# Conn_pcb6.net
KiCad netlist of a schematic drawn in EAGLE
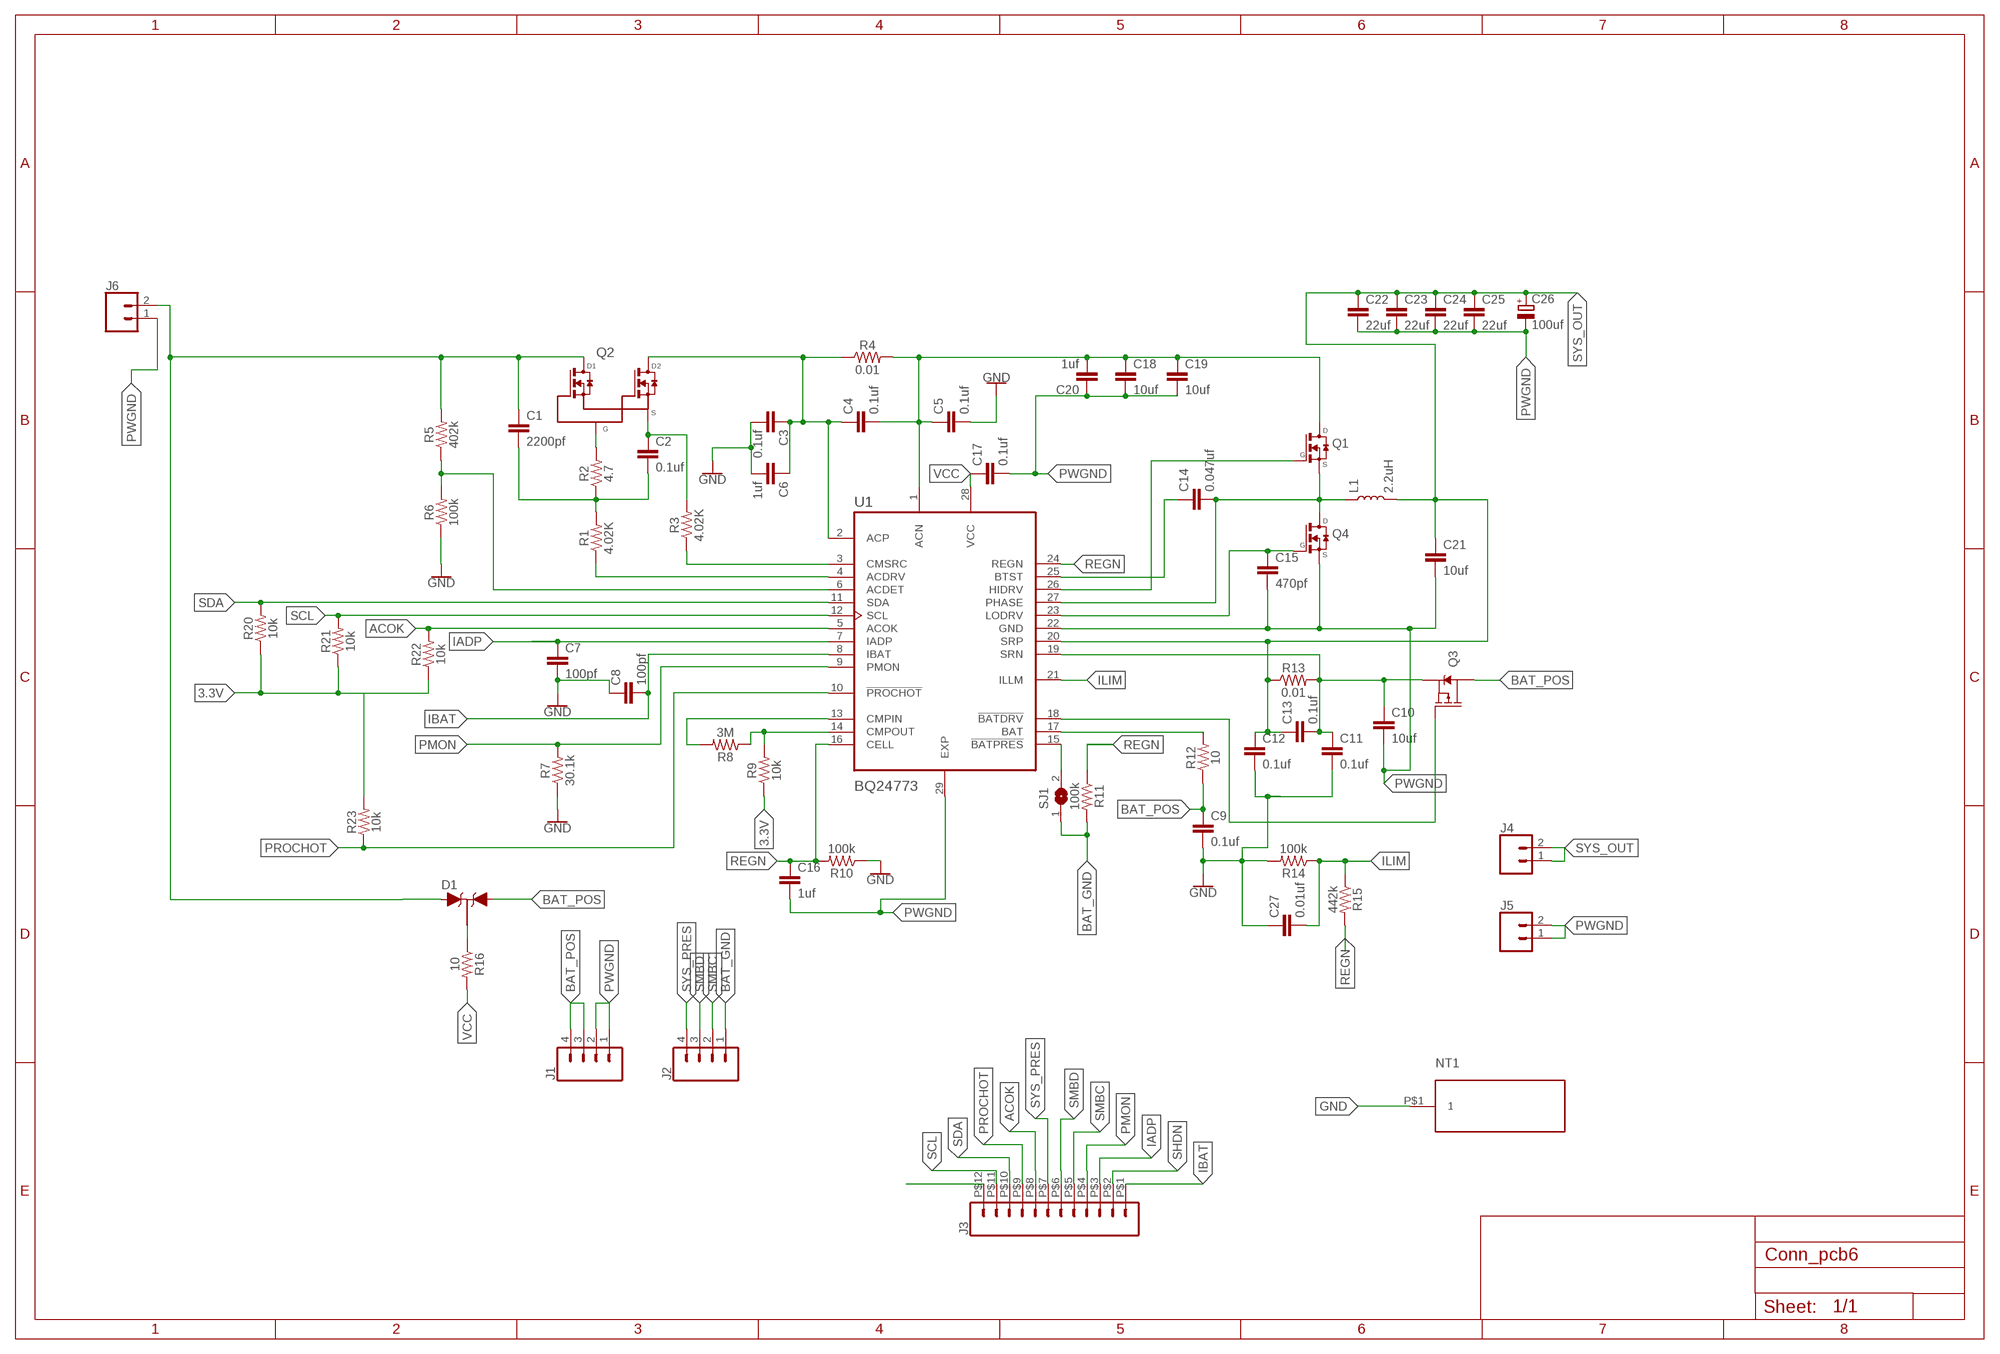
[diagram p0: schematic, sheet 1]

(export (version "E")
  (design (tool "Eeschema 10.0.6"))
  (components
    (comp (ref "C1")
      (value "2200pf")
      (footprint "eagle-import:CAPC1005X50")
      (libsource (lib "eagle-import") (part "CAP0402"))
    )
    (comp (ref "C2")
      (value "0.1uf")
      (footprint "eagle-import:CAPC1005X50")
      (libsource (lib "eagle-import") (part "CAP0402"))
    )
    (comp (ref "C3")
      (value "0.1uf")
      (footprint "eagle-import:CAPC1005X50")
      (libsource (lib "eagle-import") (part "CAP0402"))
    )
    (comp (ref "C4")
      (value "0.1uf")
      (footprint "eagle-import:CAPC1005X50")
      (libsource (lib "eagle-import") (part "CAP0402"))
    )
    (comp (ref "C5")
      (value "0.1uf")
      (footprint "eagle-import:CAPC1005X50")
      (libsource (lib "eagle-import") (part "CAP0402"))
    )
    (comp (ref "C6")
      (value "1uf")
      (footprint "eagle-import:CAPC1005X50")
      (libsource (lib "eagle-import") (part "CAP0402"))
    )
    (comp (ref "C7")
      (value "100pf")
      (footprint "eagle-import:CAPC1005X50")
      (libsource (lib "eagle-import") (part "CAP0402"))
    )
    (comp (ref "C8")
      (value "100pf")
      (footprint "eagle-import:CAPC1005X50")
      (libsource (lib "eagle-import") (part "CAP0402"))
    )
    (comp (ref "C9")
      (value "0.1uf")
      (footprint "eagle-import:CAPC1005X50")
      (libsource (lib "eagle-import") (part "CAP0402"))
    )
    (comp (ref "C10")
      (value "10uf")
      (footprint "eagle-import:C0805K")
      (libsource (lib "eagle-import") (part "C-EUC0805K"))
    )
    (comp (ref "C11")
      (value "0.1uf")
      (footprint "eagle-import:CAPC1005X50")
      (libsource (lib "eagle-import") (part "CAP0402"))
    )
    (comp (ref "C12")
      (value "0.1uf")
      (footprint "eagle-import:CAPC1005X50")
      (libsource (lib "eagle-import") (part "CAP0402"))
    )
    (comp (ref "C13")
      (value "0.1uf")
      (footprint "eagle-import:CAPC1005X50")
      (libsource (lib "eagle-import") (part "CAP0402"))
    )
    (comp (ref "C14")
      (value "0.047uf")
      (footprint "eagle-import:CAPC1005X50")
      (libsource (lib "eagle-import") (part "CAP0402"))
    )
    (comp (ref "C15")
      (value "470pf")
      (footprint "eagle-import:CAPC1005X50")
      (libsource (lib "eagle-import") (part "CAP0402"))
    )
    (comp (ref "C16")
      (value "1uf")
      (footprint "eagle-import:CAPC1005X50")
      (libsource (lib "eagle-import") (part "CAP0402"))
    )
    (comp (ref "C17")
      (value "0.1uf")
      (footprint "eagle-import:CAPC1005X50")
      (libsource (lib "eagle-import") (part "CAP0402"))
    )
    (comp (ref "C18")
      (value "10uf")
      (footprint "eagle-import:C0805K")
      (libsource (lib "eagle-import") (part "C-EUC0805K"))
    )
    (comp (ref "C19")
      (value "10uf")
      (footprint "eagle-import:C0805K")
      (libsource (lib "eagle-import") (part "C-EUC0805K"))
    )
    (comp (ref "C20")
      (value "1uf")
      (footprint "eagle-import:CAPC1005X50")
      (libsource (lib "eagle-import") (part "CAP0402"))
    )
    (comp (ref "C21")
      (value "10uf")
      (footprint "eagle-import:C0805K")
      (libsource (lib "eagle-import") (part "C-EUC0805K"))
    )
    (comp (ref "C22")
      (value "22uf")
      (footprint "eagle-import:C1206")
      (libsource (lib "eagle-import") (part "C-EUC1206"))
    )
    (comp (ref "C23")
      (value "22uf")
      (footprint "eagle-import:C1206")
      (libsource (lib "eagle-import") (part "C-EUC1206"))
    )
    (comp (ref "C24")
      (value "22uf")
      (footprint "eagle-import:C1206")
      (libsource (lib "eagle-import") (part "C-EUC1206"))
    )
    (comp (ref "C25")
      (value "22uf")
      (footprint "eagle-import:C1206")
      (libsource (lib "eagle-import") (part "C-EUC1206"))
    )
    (comp (ref "C26")
      (value "100uf")
      (footprint "eagle-import:CAPAE660X800")
      (libsource (lib "eagle-import") (part "EMZR250ARA221MF80G"))
    )
    (comp (ref "C27")
      (value "0.01uf")
      (footprint "eagle-import:CAPC1005X50")
      (libsource (lib "eagle-import") (part "CAP0402"))
    )
    (comp (ref "D1")
      (value "BAT54C-7-F")
      (footprint "eagle-import:SOT95P235X110-3")
      (libsource (lib "eagle-import") (part "BAT54C-7-F"))
    )
    (comp (ref "J1")
      (value "CONN_041.3")
      (footprint "eagle-import:1X04_NO_SILK_1.3")
      (libsource (lib "eagle-import") (part "CONN_041.3"))
    )
    (comp (ref "J2")
      (value "CONN_041.3")
      (footprint "eagle-import:1X04_NO_SILK_1.3")
      (libsource (lib "eagle-import") (part "CONN_041.3"))
    )
    (comp (ref "J3")
      (value "62674-121121ALF")
      (footprint "eagle-import:62674-121121ALF")
      (libsource (lib "eagle-import") (part "62674-121121ALF"))
    )
    (comp (ref "J4")
      (value "CONN_021.4HOLE")
      (footprint "eagle-import:1X02_1.4HOLE")
      (libsource (lib "eagle-import") (part "CONN_021.4HOLE"))
    )
    (comp (ref "J5")
      (value "CONN_021.4HOLE")
      (footprint "eagle-import:1X02_1.4HOLE")
      (libsource (lib "eagle-import") (part "CONN_021.4HOLE"))
    )
    (comp (ref "J6")
      (value "CONN_021.4HOLE")
      (footprint "eagle-import:1X02_1.4HOLE")
      (libsource (lib "eagle-import") (part "CONN_021.4HOLE"))
    )
    (comp (ref "L1")
      (value "2.2uH")
      (footprint "eagle-import:RESM6365X610")
      (libsource (lib "eagle-import") (part "XEL6060-222MEB"))
    )
    (comp (ref "NT1")
      (value "NET_TIE")
      (footprint "eagle-import:NET_TIE")
      (libsource (lib "eagle-import") (part "NET_TIE"))
    )
    (comp (ref "Q1")
      (value "CSD17308Q3")
      (footprint "eagle-import:SON65P330X330X110-8")
      (fields (field (name "SPICEPREFIX") "Q"))
      (libsource (lib "eagle-import") (part "CSD17308Q3"))
    )
    (comp (ref "Q2")
      (value "CSD87312Q3EVSON")
      (footprint "eagle-import:QFN65P330X330X100-12")
      (libsource (lib "eagle-import") (part "CSD87312Q3EVSON"))
    )
    (comp (ref "Q3")
      (value "CSD25402Q3A")
      (footprint "eagle-import:CSD25402Q3A")
      (libsource (lib "eagle-import") (part "CSD25402Q3A"))
    )
    (comp (ref "Q4")
      (value "CSD17308Q3")
      (footprint "eagle-import:SON65P330X330X110-8")
      (fields (field (name "SPICEPREFIX") "Q"))
      (libsource (lib "eagle-import") (part "CSD17308Q3"))
    )
    (comp (ref "R1")
      (value "4.02K")
      (footprint "eagle-import:0402")
      (libsource (lib "eagle-import") (part "RES4K04020402"))
    )
    (comp (ref "R2")
      (value "4.7")
      (footprint "eagle-import:0402")
      (libsource (lib "eagle-import") (part "RES4K04020402"))
    )
    (comp (ref "R3")
      (value "4.02K")
      (footprint "eagle-import:0402")
      (libsource (lib "eagle-import") (part "RES4K04020402"))
    )
    (comp (ref "R4")
      (value "0.01")
      (footprint "eagle-import:1206")
      (libsource (lib "eagle-import") (part "SENSE-RES"))
    )
    (comp (ref "R5")
      (value "402k")
      (footprint "eagle-import:0402")
      (libsource (lib "eagle-import") (part "RES4K04020402"))
    )
    (comp (ref "R6")
      (value "100k")
      (footprint "eagle-import:0402")
      (libsource (lib "eagle-import") (part "RES4K04020402"))
    )
    (comp (ref "R7")
      (value "30.1k")
      (footprint "eagle-import:0402")
      (libsource (lib "eagle-import") (part "RES4K04020402"))
    )
    (comp (ref "R8")
      (value "3M")
      (footprint "eagle-import:0402")
      (libsource (lib "eagle-import") (part "RES4K04020402"))
    )
    (comp (ref "R9")
      (value "10k")
      (footprint "eagle-import:0402")
      (libsource (lib "eagle-import") (part "RES4K04020402"))
    )
    (comp (ref "R10")
      (value "100k")
      (footprint "eagle-import:0402")
      (libsource (lib "eagle-import") (part "RES4K04020402"))
    )
    (comp (ref "R11")
      (value "100k")
      (footprint "eagle-import:0402")
      (libsource (lib "eagle-import") (part "RES4K04020402"))
    )
    (comp (ref "R12")
      (value "10")
      (footprint "eagle-import:0402")
      (libsource (lib "eagle-import") (part "RES4K04020402"))
    )
    (comp (ref "R13")
      (value "0.01")
      (footprint "eagle-import:1206")
      (libsource (lib "eagle-import") (part "SENSE-RES"))
    )
    (comp (ref "R14")
      (value "100k")
      (footprint "eagle-import:0402")
      (libsource (lib "eagle-import") (part "RES4K04020402"))
    )
    (comp (ref "R15")
      (value "442k")
      (footprint "eagle-import:0402")
      (libsource (lib "eagle-import") (part "RES4K04020402"))
    )
    (comp (ref "R16")
      (value "10")
      (footprint "eagle-import:0402")
      (libsource (lib "eagle-import") (part "RES4K04020402"))
    )
    (comp (ref "R20")
      (value "10k")
      (footprint "eagle-import:0402")
      (libsource (lib "eagle-import") (part "RES4K04020402"))
    )
    (comp (ref "R21")
      (value "10k")
      (footprint "eagle-import:0402")
      (libsource (lib "eagle-import") (part "RES4K04020402"))
    )
    (comp (ref "R22")
      (value "10k")
      (footprint "eagle-import:0402")
      (libsource (lib "eagle-import") (part "RES4K04020402"))
    )
    (comp (ref "R23")
      (value "10k")
      (footprint "eagle-import:0402")
      (libsource (lib "eagle-import") (part "RES4K04020402"))
    )
    (comp (ref "SJ1") (value "SJ") (footprint "eagle-import:SJ") (libsource (lib "eagle-import") (part "SJ")))
    (comp (ref "U1")
      (value "BQ24773")
      (footprint "eagle-import:QFN40P400X400X80-29T240")
      (libsource (lib "eagle-import") (part "BQ24773"))
    )
  )
  (nets
    (net (code "1") (name "3.3V") (class "Default")
      (node (ref "R20") (pin "1") (pinfunction "1_1") (pintype "passive"))
      (node (ref "R21") (pin "1") (pinfunction "1_1") (pintype "passive"))
      (node (ref "R22") (pin "1") (pinfunction "1_1") (pintype "passive"))
      (node (ref "R23") (pin "2") (pinfunction "2_2") (pintype "passive"))
      (node (ref "R9") (pin "1") (pinfunction "1_1") (pintype "passive"))
    )
    (net (code "2") (name "ACOK") (class "Default")
      (node (ref "J3") (pin "P$8") (pinfunction "8_P$8") (pintype "passive"))
      (node (ref "R22") (pin "2") (pinfunction "2_2") (pintype "passive"))
      (node (ref "U1") (pin "5") (pinfunction "ACOK_5") (pintype "output"))
    )
    (net (code "3") (name "BAT_GND") (class "Default")
      (node (ref "J2") (pin "1") (pinfunction "1_1") (pintype "passive"))
      (node (ref "R11") (pin "2") (pinfunction "2_2") (pintype "passive"))
      (node (ref "SJ1") (pin "1") (pinfunction "1_1") (pintype "passive"))
    )
    (net (code "4") (name "BAT_POS") (class "Default")
      (node (ref "C9") (pin "1") (pinfunction "1_1") (pintype "passive"))
      (node (ref "D1") (pin "2") (pinfunction "A2_2") (pintype "passive"))
      (node (ref "J1") (pin "3") (pinfunction "3_3") (pintype "passive"))
      (node (ref "J1") (pin "4") (pinfunction "4_4") (pintype "passive"))
      (node (ref "Q3") (pin "1") (pinfunction "D_1") (pintype "bidirectional"))
      (node (ref "Q3") (pin "2") (pinfunction "D_2") (pintype "bidirectional"))
      (node (ref "Q3") (pin "3") (pinfunction "D_3") (pintype "bidirectional"))
      (node (ref "R12") (pin "1") (pinfunction "1_1") (pintype "passive"))
    )
    (net (code "5") (name "GND") (class "Default")
      (node (ref "C11") (pin "2") (pinfunction "2_2") (pintype "passive"))
      (node (ref "C12") (pin "2") (pinfunction "2_2") (pintype "passive"))
      (node (ref "C27") (pin "1") (pinfunction "1_1") (pintype "passive"))
      (node (ref "C3") (pin "2") (pinfunction "2_2") (pintype "passive"))
      (node (ref "C5") (pin "2") (pinfunction "2_2") (pintype "passive"))
      (node (ref "C6") (pin "2") (pinfunction "2_2") (pintype "passive"))
      (node (ref "C7") (pin "2") (pinfunction "2_2") (pintype "passive"))
      (node (ref "C8") (pin "1") (pinfunction "1_1") (pintype "passive"))
      (node (ref "C9") (pin "2") (pinfunction "2_2") (pintype "passive"))
      (node (ref "NT1") (pin "P$1") (pinfunction "1_P$1") (pintype "bidirectional"))
      (node (ref "R10") (pin "1") (pinfunction "1_1") (pintype "passive"))
      (node (ref "R14") (pin "2") (pinfunction "2_2") (pintype "passive"))
      (node (ref "R6") (pin "1") (pinfunction "1_1") (pintype "passive"))
      (node (ref "R7") (pin "1") (pinfunction "1_1") (pintype "passive"))
    )
    (net (code "6") (name "IADP") (class "Default")
      (node (ref "C7") (pin "1") (pinfunction "1_1") (pintype "passive"))
      (node (ref "J3") (pin "P$3") (pinfunction "3_P$3") (pintype "passive"))
      (node (ref "U1") (pin "7") (pinfunction "IADP_7") (pintype "output"))
    )
    (net (code "7") (name "IBAT") (class "Default")
      (node (ref "C8") (pin "2") (pinfunction "2_2") (pintype "passive"))
      (node (ref "J3") (pin "P$1") (pinfunction "1_P$1") (pintype "passive"))
      (node (ref "U1") (pin "8") (pinfunction "IBAT_8") (pintype "output"))
    )
    (net (code "8") (name "ILIM") (class "Default")
      (node (ref "C27") (pin "2") (pinfunction "2_2") (pintype "passive"))
      (node (ref "R14") (pin "1") (pinfunction "1_1") (pintype "passive"))
      (node (ref "R15") (pin "1") (pinfunction "1_1") (pintype "passive"))
      (node (ref "U1") (pin "21") (pinfunction "ILLM_21") (pintype "input"))
    )
    (net (code "9") (name "Net-(C1-Pad2)") (class "Default")
      (node (ref "C1") (pin "2") (pinfunction "2_2") (pintype "passive"))
      (node (ref "C2") (pin "2") (pinfunction "2_2") (pintype "passive"))
      (node (ref "R1") (pin "2") (pinfunction "2_2") (pintype "passive"))
      (node (ref "R2") (pin "1") (pinfunction "1_1") (pintype "passive"))
    )
    (net (code "10") (name "Net-(C2-Pad1)") (class "Default")
      (node (ref "C2") (pin "1") (pinfunction "1_1") (pintype "passive"))
      (node (ref "Q2") (pin "9") (pinfunction "S_9") (pintype "passive"))
      (node (ref "Q2") (pin "9.1") (pinfunction "S_9.1") (pintype "passive"))
      (node (ref "Q2") (pin "9.2") (pinfunction "S_9.2") (pintype "passive"))
      (node (ref "Q2") (pin "9.3") (pinfunction "S_9.3") (pintype "passive"))
      (node (ref "Q2") (pin "9.4") (pinfunction "S_9.4") (pintype "passive"))
      (node (ref "R3") (pin "2") (pinfunction "2_2") (pintype "passive"))
    )
    (net (code "11") (name "Net-(D1-A1)") (class "Default")
      (node (ref "C1") (pin "1") (pinfunction "1_1") (pintype "passive"))
      (node (ref "D1") (pin "1") (pinfunction "A1_1") (pintype "passive"))
      (node (ref "J6") (pin "2") (pinfunction "2_2") (pintype "passive"))
      (node (ref "Q2") (pin "1") (pinfunction "D1_1") (pintype "passive"))
      (node (ref "Q2") (pin "3") (pinfunction "D1_3") (pintype "passive"))
      (node (ref "Q2") (pin "4") (pinfunction "D1_4") (pintype "passive"))
      (node (ref "R5") (pin "2") (pinfunction "2_2") (pintype "passive"))
    )
    (net (code "12") (name "Net-(D1-K)") (class "Default")
      (node (ref "D1") (pin "3") (pinfunction "K_3") (pintype "passive"))
      (node (ref "R16") (pin "1") (pinfunction "1_1") (pintype "passive"))
    )
    (net (code "13") (name "Net-(Q1-G)") (class "Default")
      (node (ref "Q1") (pin "4") (pinfunction "G_4") (pintype "passive"))
      (node (ref "U1") (pin "26") (pinfunction "HIDRV_26") (pintype "output"))
    )
    (net (code "14") (name "Net-(Q2-G)") (class "Default")
      (node (ref "Q2") (pin "5") (pinfunction "G_5") (pintype "passive"))
      (node (ref "R2") (pin "2") (pinfunction "2_2") (pintype "passive"))
    )
    (net (code "15") (name "Net-(Q3-G)") (class "Default")
      (node (ref "Q3") (pin "4") (pinfunction "G_4") (pintype "bidirectional"))
      (node (ref "U1") (pin "18") (pinfunction "~{BATDRV}_18") (pintype "output"))
    )
    (net (code "16") (name "Net-(Q4-G)") (class "Default")
      (node (ref "C15") (pin "1") (pinfunction "1_1") (pintype "passive"))
      (node (ref "Q4") (pin "4") (pinfunction "G_4") (pintype "passive"))
      (node (ref "U1") (pin "23") (pinfunction "LODRV_23") (pintype "output"))
    )
    (net (code "17") (name "Net-(U1-ACDET)") (class "Default")
      (node (ref "R5") (pin "1") (pinfunction "1_1") (pintype "passive"))
      (node (ref "R6") (pin "2") (pinfunction "2_2") (pintype "passive"))
      (node (ref "U1") (pin "6") (pinfunction "ACDET_6") (pintype "input"))
    )
    (net (code "18") (name "Net-(U1-ACDRV)") (class "Default")
      (node (ref "R1") (pin "1") (pinfunction "1_1") (pintype "passive"))
      (node (ref "U1") (pin "4") (pinfunction "ACDRV_4") (pintype "output"))
    )
    (net (code "19") (name "Net-(U1-ACN)") (class "Default")
      (node (ref "C18") (pin "1") (pinfunction "1_1") (pintype "passive"))
      (node (ref "C19") (pin "1") (pinfunction "1_1") (pintype "passive"))
      (node (ref "C20") (pin "2") (pinfunction "2_2") (pintype "passive"))
      (node (ref "C4") (pin "2") (pinfunction "2_2") (pintype "passive"))
      (node (ref "C5") (pin "1") (pinfunction "1_1") (pintype "passive"))
      (node (ref "Q1") (pin "5") (pinfunction "D_5") (pintype "passive"))
      (node (ref "Q1") (pin "6") (pinfunction "D_6") (pintype "passive"))
      (node (ref "Q1") (pin "7") (pinfunction "D_7") (pintype "passive"))
      (node (ref "Q1") (pin "8") (pinfunction "D_8") (pintype "passive"))
      (node (ref "R4") (pin "2") (pinfunction "2_2") (pintype "passive"))
      (node (ref "U1") (pin "1") (pinfunction "ACN_1") (pintype "input"))
    )
    (net (code "20") (name "Net-(U1-ACP)") (class "Default")
      (node (ref "C3") (pin "1") (pinfunction "1_1") (pintype "passive"))
      (node (ref "C4") (pin "1") (pinfunction "1_1") (pintype "passive"))
      (node (ref "C6") (pin "1") (pinfunction "1_1") (pintype "passive"))
      (node (ref "Q2") (pin "6") (pinfunction "D2_6") (pintype "passive"))
      (node (ref "Q2") (pin "7") (pinfunction "D2_7") (pintype "passive"))
      (node (ref "Q2") (pin "8") (pinfunction "D2_8") (pintype "passive"))
      (node (ref "R4") (pin "1") (pinfunction "1_1") (pintype "passive"))
      (node (ref "U1") (pin "2") (pinfunction "ACP_2") (pintype "input"))
    )
    (net (code "21") (name "Net-(U1-BAT)") (class "Default")
      (node (ref "R12") (pin "2") (pinfunction "2_2") (pintype "passive"))
      (node (ref "U1") (pin "17") (pinfunction "BAT_17") (pintype "input"))
    )
    (net (code "22") (name "Net-(U1-BTST)") (class "Default")
      (node (ref "C14") (pin "1") (pinfunction "1_1") (pintype "passive"))
      (node (ref "U1") (pin "25") (pinfunction "BTST_25") (pintype "passive"))
    )
    (net (code "23") (name "Net-(U1-CMPIN)") (class "Default")
      (node (ref "R8") (pin "2") (pinfunction "2_2") (pintype "passive"))
      (node (ref "U1") (pin "13") (pinfunction "CMPIN_13") (pintype "input"))
    )
    (net (code "24") (name "Net-(U1-CMPOUT)") (class "Default")
      (node (ref "R8") (pin "1") (pinfunction "1_1") (pintype "passive"))
      (node (ref "R9") (pin "2") (pinfunction "2_2") (pintype "passive"))
      (node (ref "U1") (pin "14") (pinfunction "CMPOUT_14") (pintype "output"))
    )
    (net (code "25") (name "Net-(U1-CMSRC)") (class "Default")
      (node (ref "R3") (pin "1") (pinfunction "1_1") (pintype "passive"))
      (node (ref "U1") (pin "3") (pinfunction "CMSRC_3") (pintype "input"))
    )
    (net (code "26") (name "Net-(U1-PHASE)") (class "Default")
      (node (ref "C14") (pin "2") (pinfunction "2_2") (pintype "passive"))
      (node (ref "L1") (pin "1") (pinfunction "1_1") (pintype "passive"))
      (node (ref "Q1") (pin "1") (pinfunction "S_1") (pintype "passive"))
      (node (ref "Q1") (pin "2") (pinfunction "S_2") (pintype "passive"))
      (node (ref "Q1") (pin "3") (pinfunction "S_3") (pintype "passive"))
      (node (ref "Q4") (pin "5") (pinfunction "D_5") (pintype "passive"))
      (node (ref "Q4") (pin "6") (pinfunction "D_6") (pintype "passive"))
      (node (ref "Q4") (pin "7") (pinfunction "D_7") (pintype "passive"))
      (node (ref "Q4") (pin "8") (pinfunction "D_8") (pintype "passive"))
      (node (ref "U1") (pin "27") (pinfunction "PHASE_27") (pintype "output"))
    )
    (net (code "27") (name "Net-(U1-SRN)") (class "Default")
      (node (ref "C10") (pin "1") (pinfunction "1_1") (pintype "passive"))
      (node (ref "C11") (pin "1") (pinfunction "1_1") (pintype "passive"))
      (node (ref "C13") (pin "2") (pinfunction "2_2") (pintype "passive"))
      (node (ref "Q3") (pin "5") (pinfunction "S_5") (pintype "bidirectional"))
      (node (ref "Q3") (pin "6") (pinfunction "S_6") (pintype "bidirectional"))
      (node (ref "Q3") (pin "7") (pinfunction "S_7") (pintype "bidirectional"))
      (node (ref "Q3") (pin "8") (pinfunction "S_8") (pintype "bidirectional"))
      (node (ref "Q3") (pin "9") (pinfunction "S_9") (pintype "bidirectional"))
      (node (ref "R13") (pin "2") (pinfunction "2_2") (pintype "passive"))
      (node (ref "U1") (pin "19") (pinfunction "SRN_19") (pintype "input"))
    )
    (net (code "28") (name "Net-(U1-~{BATPRES})") (class "Default")
      (node (ref "SJ1") (pin "2") (pinfunction "2_2") (pintype "passive"))
      (node (ref "U1") (pin "15") (pinfunction "~{BATPRES}_15") (pintype "input"))
    )
    (net (code "29") (name "PMON") (class "Default")
      (node (ref "J3") (pin "P$4") (pinfunction "4_P$4") (pintype "passive"))
      (node (ref "R7") (pin "2") (pinfunction "2_2") (pintype "passive"))
      (node (ref "U1") (pin "9") (pinfunction "PMON_9") (pintype "output"))
    )
    (net (code "30") (name "PROCHOT") (class "Default")
      (node (ref "J3") (pin "P$9") (pinfunction "9_P$9") (pintype "passive"))
      (node (ref "R23") (pin "1") (pinfunction "1_1") (pintype "passive"))
      (node (ref "U1") (pin "10") (pinfunction "~{PROCHOT}_10") (pintype "output"))
    )
    (net (code "31") (name "PWGND") (class "Default")
      (node (ref "C10") (pin "2") (pinfunction "2_2") (pintype "passive"))
      (node (ref "C15") (pin "2") (pinfunction "2_2") (pintype "passive"))
      (node (ref "C16") (pin "2") (pinfunction "2_2") (pintype "passive"))
      (node (ref "C17") (pin "2") (pinfunction "2_2") (pintype "passive"))
      (node (ref "C18") (pin "2") (pinfunction "2_2") (pintype "passive"))
      (node (ref "C19") (pin "2") (pinfunction "2_2") (pintype "passive"))
      (node (ref "C20") (pin "1") (pinfunction "1_1") (pintype "passive"))
      (node (ref "C21") (pin "2") (pinfunction "2_2") (pintype "passive"))
      (node (ref "C22") (pin "2") (pinfunction "2_2") (pintype "passive"))
      (node (ref "C23") (pin "2") (pinfunction "2_2") (pintype "passive"))
      (node (ref "C24") (pin "2") (pinfunction "2_2") (pintype "passive"))
      (node (ref "C25") (pin "2") (pinfunction "2_2") (pintype "passive"))
      (node (ref "C26") (pin "2") (pinfunction "-_2") (pintype "passive"))
      (node (ref "J1") (pin "1") (pinfunction "1_1") (pintype "passive"))
      (node (ref "J1") (pin "2") (pinfunction "2_2") (pintype "passive"))
      (node (ref "J5") (pin "1") (pinfunction "1_1") (pintype "passive"))
      (node (ref "J5") (pin "2") (pinfunction "2_2") (pintype "passive"))
      (node (ref "J6") (pin "1") (pinfunction "1_1") (pintype "passive"))
      (node (ref "Q4") (pin "1") (pinfunction "S_1") (pintype "passive"))
      (node (ref "Q4") (pin "2") (pinfunction "S_2") (pintype "passive"))
      (node (ref "Q4") (pin "3") (pinfunction "S_3") (pintype "passive"))
      (node (ref "U1") (pin "22") (pinfunction "GND_22") (pintype "power_in"))
      (node (ref "U1") (pin "29") (pinfunction "EXP_29") (pintype "power_in"))
    )
    (net (code "32") (name "REGN") (class "Default")
      (node (ref "C16") (pin "1") (pinfunction "1_1") (pintype "passive"))
      (node (ref "R10") (pin "2") (pinfunction "2_2") (pintype "passive"))
      (node (ref "R11") (pin "1") (pinfunction "1_1") (pintype "passive"))
      (node (ref "R15") (pin "2") (pinfunction "2_2") (pintype "passive"))
      (node (ref "U1") (pin "16") (pinfunction "CELL_16") (pintype "input"))
      (node (ref "U1") (pin "24") (pinfunction "REGN_24") (pintype "output"))
    )
    (net (code "33") (name "SCL") (class "Default")
      (node (ref "J3") (pin "P$11") (pinfunction "11_P$11") (pintype "passive"))
      (node (ref "R21") (pin "2") (pinfunction "2_2") (pintype "passive"))
      (node (ref "U1") (pin "12") (pinfunction "SCL_12") (pintype "input"))
    )
    (net (code "34") (name "SDA") (class "Default")
      (node (ref "J3") (pin "P$10") (pinfunction "10_P$10") (pintype "passive"))
      (node (ref "R20") (pin "2") (pinfunction "2_2") (pintype "passive"))
      (node (ref "U1") (pin "11") (pinfunction "SDA_11") (pintype "bidirectional"))
    )
    (net (code "35") (name "SHDN") (class "Default")
      (node (ref "J3") (pin "P$2") (pinfunction "2_P$2") (pintype "passive"))
    )
    (net (code "36") (name "SMBC") (class "Default")
      (node (ref "J2") (pin "2") (pinfunction "2_2") (pintype "passive"))
      (node (ref "J3") (pin "P$5") (pinfunction "5_P$5") (pintype "passive"))
    )
    (net (code "37") (name "SMBD") (class "Default")
      (node (ref "J2") (pin "3") (pinfunction "3_3") (pintype "passive"))
      (node (ref "J3") (pin "P$6") (pinfunction "6_P$6") (pintype "passive"))
    )
    (net (code "38") (name "SYS_OUT") (class "Default")
      (node (ref "C12") (pin "1") (pinfunction "1_1") (pintype "passive"))
      (node (ref "C13") (pin "1") (pinfunction "1_1") (pintype "passive"))
      (node (ref "C21") (pin "1") (pinfunction "1_1") (pintype "passive"))
      (node (ref "C22") (pin "1") (pinfunction "1_1") (pintype "passive"))
      (node (ref "C23") (pin "1") (pinfunction "1_1") (pintype "passive"))
      (node (ref "C24") (pin "1") (pinfunction "1_1") (pintype "passive"))
      (node (ref "C25") (pin "1") (pinfunction "1_1") (pintype "passive"))
      (node (ref "C26") (pin "1") (pinfunction "+_1") (pintype "passive"))
      (node (ref "J4") (pin "1") (pinfunction "1_1") (pintype "passive"))
      (node (ref "J4") (pin "2") (pinfunction "2_2") (pintype "passive"))
      (node (ref "L1") (pin "2") (pinfunction "2_2") (pintype "passive"))
      (node (ref "R13") (pin "1") (pinfunction "1_1") (pintype "passive"))
      (node (ref "U1") (pin "20") (pinfunction "SRP_20") (pintype "input"))
    )
    (net (code "39") (name "SYS_PRES") (class "Default")
      (node (ref "J2") (pin "4") (pinfunction "4_4") (pintype "passive"))
      (node (ref "J3") (pin "P$7") (pinfunction "7_P$7") (pintype "passive"))
    )
    (net (code "40") (name "VCC") (class "Default")
      (node (ref "C17") (pin "1") (pinfunction "1_1") (pintype "passive"))
      (node (ref "R16") (pin "2") (pinfunction "2_2") (pintype "passive"))
      (node (ref "U1") (pin "28") (pinfunction "VCC_28") (pintype "power_in"))
    )
    (net (code "41") (name "unconnected-(J3-12-PadP$12)") (class "Default")
      (node (ref "J3") (pin "P$12") (pinfunction "12_P$12") (pintype "passive"))
    )
  )
)
